# B141X.net
KiCad netlist of a schematic drawn in EAGLE
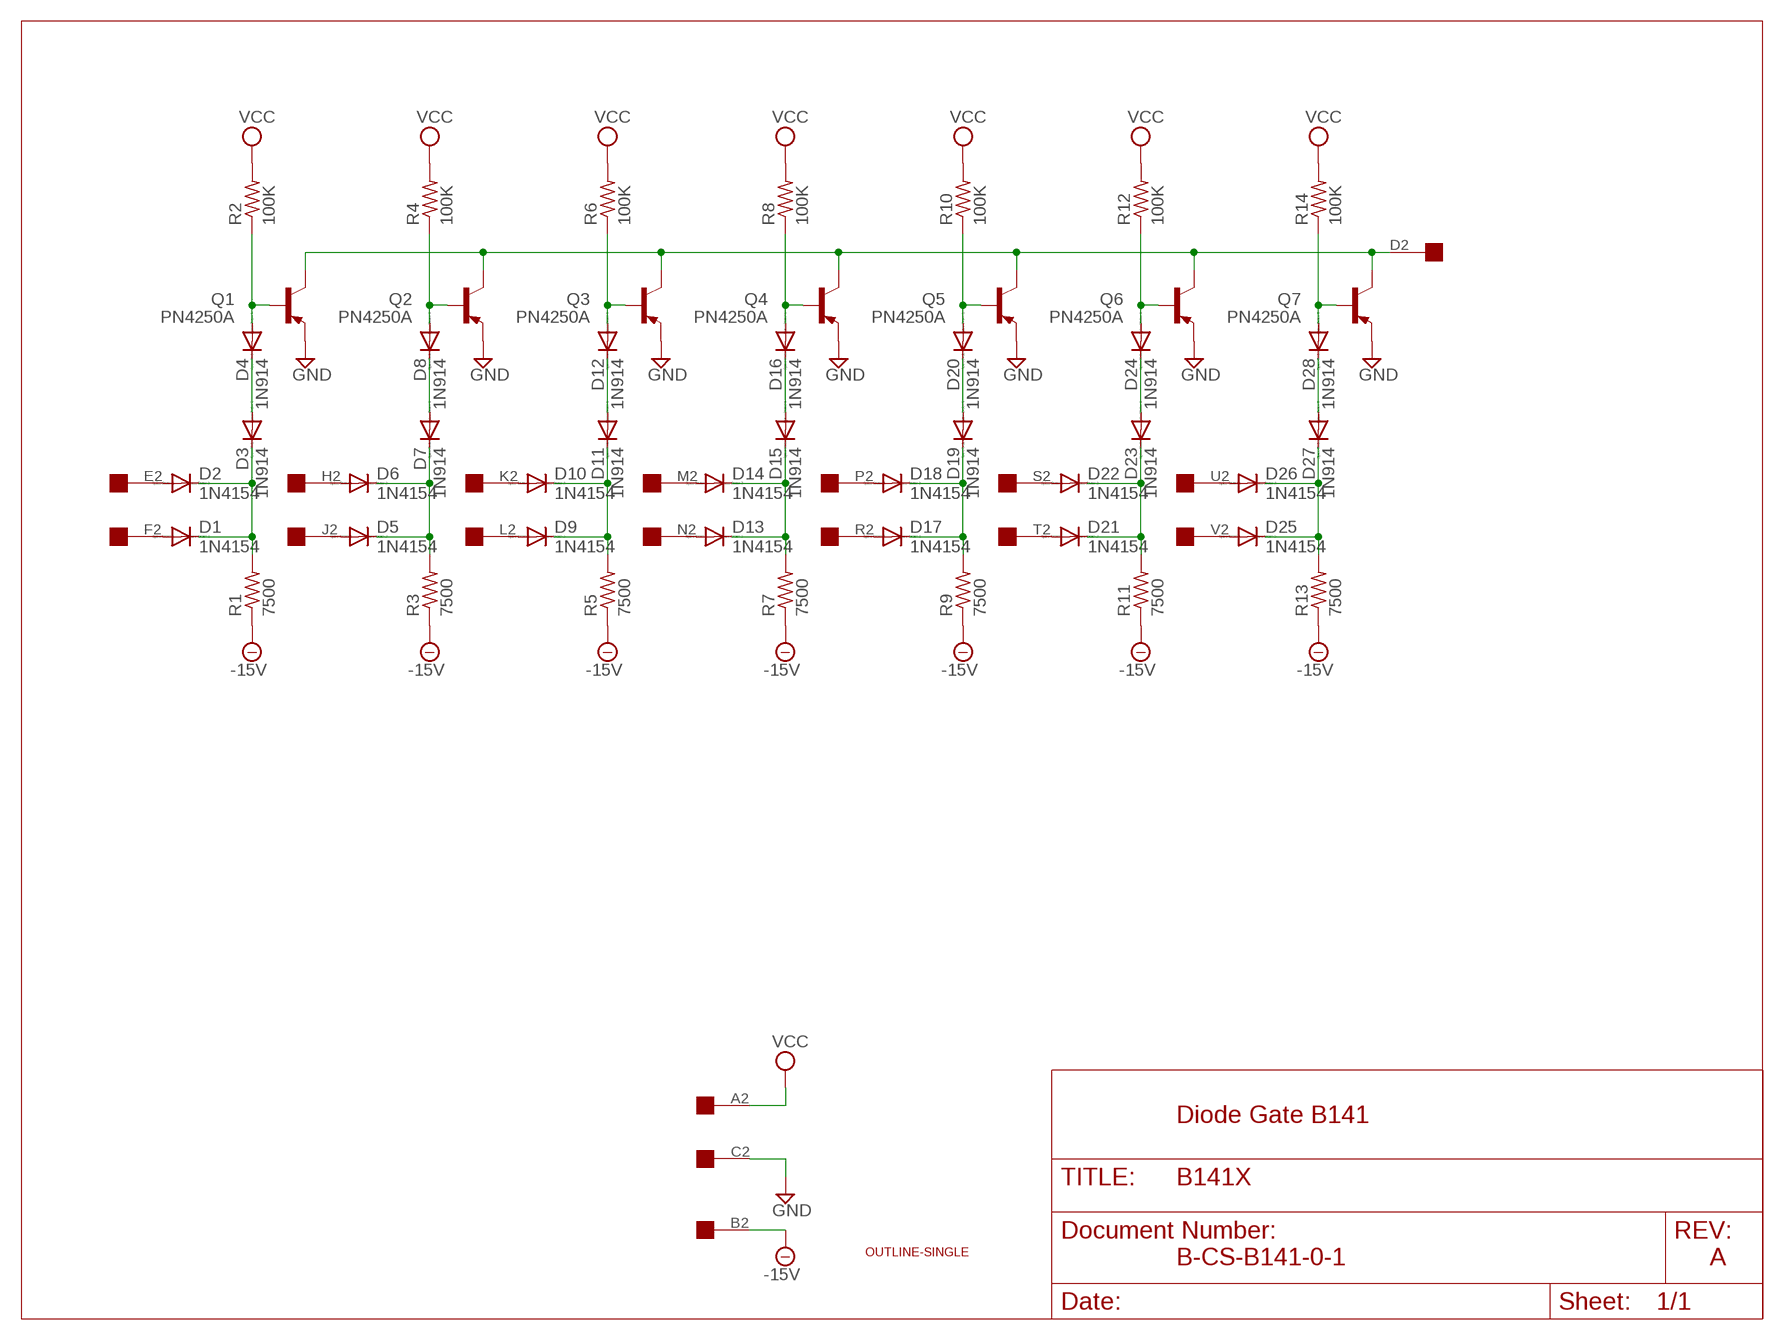
[diagram p0: schematic, sheet 1]

(export (version "E")
  (design (tool "Eeschema 10.0.6"))
  (components
    (comp (ref "D1")
      (value "1N4154")
      (footprint "eagle-import:DO35-10")
      (libsource (lib "eagle-import") (part "DIODE-DO35-10"))
    )
    (comp (ref "D2")
      (value "1N4154")
      (footprint "eagle-import:DO35-10")
      (libsource (lib "eagle-import") (part "DIODE-DO35-10"))
    )
    (comp (ref "D3")
      (value "1N914")
      (footprint "eagle-import:DO35-10")
      (libsource (lib "eagle-import") (part "DIODE-DO35-10"))
    )
    (comp (ref "D4")
      (value "1N914")
      (footprint "eagle-import:DO35-10")
      (libsource (lib "eagle-import") (part "DIODE-DO35-10"))
    )
    (comp (ref "D5")
      (value "1N4154")
      (footprint "eagle-import:DO35-10")
      (libsource (lib "eagle-import") (part "DIODE-DO35-10"))
    )
    (comp (ref "D6")
      (value "1N4154")
      (footprint "eagle-import:DO35-10")
      (libsource (lib "eagle-import") (part "DIODE-DO35-10"))
    )
    (comp (ref "D7")
      (value "1N914")
      (footprint "eagle-import:DO35-10")
      (libsource (lib "eagle-import") (part "DIODE-DO35-10"))
    )
    (comp (ref "D8")
      (value "1N914")
      (footprint "eagle-import:DO35-10")
      (libsource (lib "eagle-import") (part "DIODE-DO35-10"))
    )
    (comp (ref "D9")
      (value "1N4154")
      (footprint "eagle-import:DO35-10")
      (libsource (lib "eagle-import") (part "DIODE-DO35-10"))
    )
    (comp (ref "D10")
      (value "1N4154")
      (footprint "eagle-import:DO35-10")
      (libsource (lib "eagle-import") (part "DIODE-DO35-10"))
    )
    (comp (ref "D11")
      (value "1N914")
      (footprint "eagle-import:DO35-10")
      (libsource (lib "eagle-import") (part "DIODE-DO35-10"))
    )
    (comp (ref "D12")
      (value "1N914")
      (footprint "eagle-import:DO35-10")
      (libsource (lib "eagle-import") (part "DIODE-DO35-10"))
    )
    (comp (ref "D13")
      (value "1N4154")
      (footprint "eagle-import:DO35-10")
      (libsource (lib "eagle-import") (part "DIODE-DO35-10"))
    )
    (comp (ref "D14")
      (value "1N4154")
      (footprint "eagle-import:DO35-10")
      (libsource (lib "eagle-import") (part "DIODE-DO35-10"))
    )
    (comp (ref "D15")
      (value "1N914")
      (footprint "eagle-import:DO35-10")
      (libsource (lib "eagle-import") (part "DIODE-DO35-10"))
    )
    (comp (ref "D16")
      (value "1N914")
      (footprint "eagle-import:DO35-10")
      (libsource (lib "eagle-import") (part "DIODE-DO35-10"))
    )
    (comp (ref "D17")
      (value "1N4154")
      (footprint "eagle-import:DO35-10")
      (libsource (lib "eagle-import") (part "DIODE-DO35-10"))
    )
    (comp (ref "D18")
      (value "1N4154")
      (footprint "eagle-import:DO35-10")
      (libsource (lib "eagle-import") (part "DIODE-DO35-10"))
    )
    (comp (ref "D19")
      (value "1N914")
      (footprint "eagle-import:DO35-10")
      (libsource (lib "eagle-import") (part "DIODE-DO35-10"))
    )
    (comp (ref "D20")
      (value "1N914")
      (footprint "eagle-import:DO35-10")
      (libsource (lib "eagle-import") (part "DIODE-DO35-10"))
    )
    (comp (ref "D21")
      (value "1N4154")
      (footprint "eagle-import:DO35-10")
      (libsource (lib "eagle-import") (part "DIODE-DO35-10"))
    )
    (comp (ref "D22")
      (value "1N4154")
      (footprint "eagle-import:DO35-10")
      (libsource (lib "eagle-import") (part "DIODE-DO35-10"))
    )
    (comp (ref "D23")
      (value "1N914")
      (footprint "eagle-import:DO35-10")
      (libsource (lib "eagle-import") (part "DIODE-DO35-10"))
    )
    (comp (ref "D24")
      (value "1N914")
      (footprint "eagle-import:DO35-10")
      (libsource (lib "eagle-import") (part "DIODE-DO35-10"))
    )
    (comp (ref "D25")
      (value "1N4154")
      (footprint "eagle-import:DO35-10")
      (libsource (lib "eagle-import") (part "DIODE-DO35-10"))
    )
    (comp (ref "D26")
      (value "1N4154")
      (footprint "eagle-import:DO35-10")
      (libsource (lib "eagle-import") (part "DIODE-DO35-10"))
    )
    (comp (ref "D27")
      (value "1N914")
      (footprint "eagle-import:DO35-10")
      (libsource (lib "eagle-import") (part "DIODE-DO35-10"))
    )
    (comp (ref "D28")
      (value "1N914")
      (footprint "eagle-import:DO35-10")
      (libsource (lib "eagle-import") (part "DIODE-DO35-10"))
    )
    (comp (ref "Q1")
      (value "PN4250A")
      (footprint "eagle-import:TO5")
      (libsource (lib "eagle-import") (part "-PNP-TO5"))
    )
    (comp (ref "Q2")
      (value "PN4250A")
      (footprint "eagle-import:TO5")
      (libsource (lib "eagle-import") (part "-PNP-TO5"))
    )
    (comp (ref "Q3")
      (value "PN4250A")
      (footprint "eagle-import:TO5")
      (libsource (lib "eagle-import") (part "-PNP-TO5"))
    )
    (comp (ref "Q4")
      (value "PN4250A")
      (footprint "eagle-import:TO5")
      (libsource (lib "eagle-import") (part "-PNP-TO5"))
    )
    (comp (ref "Q5")
      (value "PN4250A")
      (footprint "eagle-import:TO5")
      (libsource (lib "eagle-import") (part "-PNP-TO5"))
    )
    (comp (ref "Q6")
      (value "PN4250A")
      (footprint "eagle-import:TO5")
      (libsource (lib "eagle-import") (part "-PNP-TO5"))
    )
    (comp (ref "Q7")
      (value "PN4250A")
      (footprint "eagle-import:TO5")
      (libsource (lib "eagle-import") (part "-PNP-TO5"))
    )
    (comp (ref "R1")
      (value "7500")
      (footprint "eagle-import:0207_10")
      (libsource (lib "eagle-import") (part "R-US_0207/10"))
    )
    (comp (ref "R2")
      (value "100K")
      (footprint "eagle-import:0207_10")
      (libsource (lib "eagle-import") (part "R-US_0207/10"))
    )
    (comp (ref "R3")
      (value "7500")
      (footprint "eagle-import:0207_10")
      (libsource (lib "eagle-import") (part "R-US_0207/10"))
    )
    (comp (ref "R4")
      (value "100K")
      (footprint "eagle-import:0207_10")
      (libsource (lib "eagle-import") (part "R-US_0207/10"))
    )
    (comp (ref "R5")
      (value "7500")
      (footprint "eagle-import:0207_10")
      (libsource (lib "eagle-import") (part "R-US_0207/10"))
    )
    (comp (ref "R6")
      (value "100K")
      (footprint "eagle-import:0207_10")
      (libsource (lib "eagle-import") (part "R-US_0207/10"))
    )
    (comp (ref "R7")
      (value "7500")
      (footprint "eagle-import:0207_10")
      (libsource (lib "eagle-import") (part "R-US_0207/10"))
    )
    (comp (ref "R8")
      (value "100K")
      (footprint "eagle-import:0207_10")
      (libsource (lib "eagle-import") (part "R-US_0207/10"))
    )
    (comp (ref "R9")
      (value "7500")
      (footprint "eagle-import:0207_10")
      (libsource (lib "eagle-import") (part "R-US_0207/10"))
    )
    (comp (ref "R10")
      (value "100K")
      (footprint "eagle-import:0207_10")
      (libsource (lib "eagle-import") (part "R-US_0207/10"))
    )
    (comp (ref "R11")
      (value "7500")
      (footprint "eagle-import:0207_10")
      (libsource (lib "eagle-import") (part "R-US_0207/10"))
    )
    (comp (ref "R12")
      (value "100K")
      (footprint "eagle-import:0207_10")
      (libsource (lib "eagle-import") (part "R-US_0207/10"))
    )
    (comp (ref "R13")
      (value "7500")
      (footprint "eagle-import:0207_10")
      (libsource (lib "eagle-import") (part "R-US_0207/10"))
    )
    (comp (ref "R14")
      (value "100K")
      (footprint "eagle-import:0207_10")
      (libsource (lib "eagle-import") (part "R-US_0207/10"))
    )
    (comp (ref "U$1")
      (value "OUTLINE-SINGLE")
      (footprint "eagle-import:SINGLE")
      (libsource (lib "eagle-import") (part "OUTLINE-SINGLE"))
    )
    (comp (ref "U$2")
      (value "EDGE-1")
      (footprint "eagle-import:EDGE-CON1")
      (libsource (lib "eagle-import") (part "EDGE-1"))
    )
  )
  (nets
    (net (code "1") (name "-15V") (class "Default")
      (node (ref "R1") (pin "1") (pinfunction "1_1") (pintype "passive"))
      (node (ref "R11") (pin "1") (pinfunction "1_1") (pintype "passive"))
      (node (ref "R13") (pin "1") (pinfunction "1_1") (pintype "passive"))
      (node (ref "R3") (pin "1") (pinfunction "1_1") (pintype "passive"))
      (node (ref "R5") (pin "1") (pinfunction "1_1") (pintype "passive"))
      (node (ref "R7") (pin "1") (pinfunction "1_1") (pintype "passive"))
      (node (ref "R9") (pin "1") (pinfunction "1_1") (pintype "passive"))
      (node (ref "U$2") (pin "B2") (pinfunction "1_B2") (pintype "bidirectional"))
    )
    (net (code "2") (name "GND") (class "Default")
      (node (ref "Q1") (pin "1") (pinfunction "E_1") (pintype "passive"))
      (node (ref "Q2") (pin "1") (pinfunction "E_1") (pintype "passive"))
      (node (ref "Q3") (pin "1") (pinfunction "E_1") (pintype "passive"))
      (node (ref "Q4") (pin "1") (pinfunction "E_1") (pintype "passive"))
      (node (ref "Q5") (pin "1") (pinfunction "E_1") (pintype "passive"))
      (node (ref "Q6") (pin "1") (pinfunction "E_1") (pintype "passive"))
      (node (ref "Q7") (pin "1") (pinfunction "E_1") (pintype "passive"))
      (node (ref "U$2") (pin "C2") (pinfunction "1_C2") (pintype "bidirectional"))
    )
    (net (code "3") (name "Net-(D1-PadC)") (class "Default")
      (node (ref "D1") (pin "C") (pinfunction "C_C") (pintype "passive"))
      (node (ref "D2") (pin "C") (pinfunction "C_C") (pintype "passive"))
      (node (ref "D3") (pin "C") (pinfunction "C_C") (pintype "passive"))
      (node (ref "R1") (pin "2") (pinfunction "2_2") (pintype "passive"))
    )
    (net (code "4") (name "Net-(D3-PadA)") (class "Default")
      (node (ref "D3") (pin "A") (pinfunction "A_A") (pintype "passive"))
      (node (ref "D4") (pin "C") (pinfunction "C_C") (pintype "passive"))
    )
    (net (code "5") (name "Net-(D5-PadC)") (class "Default")
      (node (ref "D5") (pin "C") (pinfunction "C_C") (pintype "passive"))
      (node (ref "D6") (pin "C") (pinfunction "C_C") (pintype "passive"))
      (node (ref "D7") (pin "C") (pinfunction "C_C") (pintype "passive"))
      (node (ref "R3") (pin "2") (pinfunction "2_2") (pintype "passive"))
    )
    (net (code "6") (name "Net-(D7-PadA)") (class "Default")
      (node (ref "D7") (pin "A") (pinfunction "A_A") (pintype "passive"))
      (node (ref "D8") (pin "C") (pinfunction "C_C") (pintype "passive"))
    )
    (net (code "7") (name "Net-(D10-PadC)") (class "Default")
      (node (ref "D10") (pin "C") (pinfunction "C_C") (pintype "passive"))
      (node (ref "D11") (pin "C") (pinfunction "C_C") (pintype "passive"))
      (node (ref "D9") (pin "C") (pinfunction "C_C") (pintype "passive"))
      (node (ref "R5") (pin "2") (pinfunction "2_2") (pintype "passive"))
    )
    (net (code "8") (name "Net-(D11-PadA)") (class "Default")
      (node (ref "D11") (pin "A") (pinfunction "A_A") (pintype "passive"))
      (node (ref "D12") (pin "C") (pinfunction "C_C") (pintype "passive"))
    )
    (net (code "9") (name "Net-(D13-PadC)") (class "Default")
      (node (ref "D13") (pin "C") (pinfunction "C_C") (pintype "passive"))
      (node (ref "D14") (pin "C") (pinfunction "C_C") (pintype "passive"))
      (node (ref "D15") (pin "C") (pinfunction "C_C") (pintype "passive"))
      (node (ref "R7") (pin "2") (pinfunction "2_2") (pintype "passive"))
    )
    (net (code "10") (name "Net-(D15-PadA)") (class "Default")
      (node (ref "D15") (pin "A") (pinfunction "A_A") (pintype "passive"))
      (node (ref "D16") (pin "C") (pinfunction "C_C") (pintype "passive"))
    )
    (net (code "11") (name "Net-(D17-PadC)") (class "Default")
      (node (ref "D17") (pin "C") (pinfunction "C_C") (pintype "passive"))
      (node (ref "D18") (pin "C") (pinfunction "C_C") (pintype "passive"))
      (node (ref "D19") (pin "C") (pinfunction "C_C") (pintype "passive"))
      (node (ref "R9") (pin "2") (pinfunction "2_2") (pintype "passive"))
    )
    (net (code "12") (name "Net-(D19-PadA)") (class "Default")
      (node (ref "D19") (pin "A") (pinfunction "A_A") (pintype "passive"))
      (node (ref "D20") (pin "C") (pinfunction "C_C") (pintype "passive"))
    )
    (net (code "13") (name "Net-(D21-PadC)") (class "Default")
      (node (ref "D21") (pin "C") (pinfunction "C_C") (pintype "passive"))
      (node (ref "D22") (pin "C") (pinfunction "C_C") (pintype "passive"))
      (node (ref "D23") (pin "C") (pinfunction "C_C") (pintype "passive"))
      (node (ref "R11") (pin "2") (pinfunction "2_2") (pintype "passive"))
    )
    (net (code "14") (name "Net-(D23-PadA)") (class "Default")
      (node (ref "D23") (pin "A") (pinfunction "A_A") (pintype "passive"))
      (node (ref "D24") (pin "C") (pinfunction "C_C") (pintype "passive"))
    )
    (net (code "15") (name "Net-(D25-PadC)") (class "Default")
      (node (ref "D25") (pin "C") (pinfunction "C_C") (pintype "passive"))
      (node (ref "D26") (pin "C") (pinfunction "C_C") (pintype "passive"))
      (node (ref "D27") (pin "C") (pinfunction "C_C") (pintype "passive"))
      (node (ref "R13") (pin "2") (pinfunction "2_2") (pintype "passive"))
    )
    (net (code "16") (name "Net-(D27-PadA)") (class "Default")
      (node (ref "D27") (pin "A") (pinfunction "A_A") (pintype "passive"))
      (node (ref "D28") (pin "C") (pinfunction "C_C") (pintype "passive"))
    )
    (net (code "17") (name "Net-(Q1-B)") (class "Default")
      (node (ref "D4") (pin "A") (pinfunction "A_A") (pintype "passive"))
      (node (ref "Q1") (pin "2") (pinfunction "B_2") (pintype "passive"))
      (node (ref "R2") (pin "1") (pinfunction "1_1") (pintype "passive"))
    )
    (net (code "18") (name "Net-(Q1-C)") (class "Default")
      (node (ref "Q1") (pin "3") (pinfunction "C_3") (pintype "passive"))
      (node (ref "Q2") (pin "3") (pinfunction "C_3") (pintype "passive"))
      (node (ref "Q3") (pin "3") (pinfunction "C_3") (pintype "passive"))
      (node (ref "Q4") (pin "3") (pinfunction "C_3") (pintype "passive"))
      (node (ref "Q5") (pin "3") (pinfunction "C_3") (pintype "passive"))
      (node (ref "Q6") (pin "3") (pinfunction "C_3") (pintype "passive"))
      (node (ref "Q7") (pin "3") (pinfunction "C_3") (pintype "passive"))
      (node (ref "U$2") (pin "D2") (pinfunction "1_D2") (pintype "bidirectional"))
    )
    (net (code "19") (name "Net-(Q2-B)") (class "Default")
      (node (ref "D8") (pin "A") (pinfunction "A_A") (pintype "passive"))
      (node (ref "Q2") (pin "2") (pinfunction "B_2") (pintype "passive"))
      (node (ref "R4") (pin "1") (pinfunction "1_1") (pintype "passive"))
    )
    (net (code "20") (name "Net-(Q3-B)") (class "Default")
      (node (ref "D12") (pin "A") (pinfunction "A_A") (pintype "passive"))
      (node (ref "Q3") (pin "2") (pinfunction "B_2") (pintype "passive"))
      (node (ref "R6") (pin "1") (pinfunction "1_1") (pintype "passive"))
    )
    (net (code "21") (name "Net-(Q4-B)") (class "Default")
      (node (ref "D16") (pin "A") (pinfunction "A_A") (pintype "passive"))
      (node (ref "Q4") (pin "2") (pinfunction "B_2") (pintype "passive"))
      (node (ref "R8") (pin "1") (pinfunction "1_1") (pintype "passive"))
    )
    (net (code "22") (name "Net-(Q5-B)") (class "Default")
      (node (ref "D20") (pin "A") (pinfunction "A_A") (pintype "passive"))
      (node (ref "Q5") (pin "2") (pinfunction "B_2") (pintype "passive"))
      (node (ref "R10") (pin "1") (pinfunction "1_1") (pintype "passive"))
    )
    (net (code "23") (name "Net-(Q6-B)") (class "Default")
      (node (ref "D24") (pin "A") (pinfunction "A_A") (pintype "passive"))
      (node (ref "Q6") (pin "2") (pinfunction "B_2") (pintype "passive"))
      (node (ref "R12") (pin "1") (pinfunction "1_1") (pintype "passive"))
    )
    (net (code "24") (name "Net-(Q7-B)") (class "Default")
      (node (ref "D28") (pin "A") (pinfunction "A_A") (pintype "passive"))
      (node (ref "Q7") (pin "2") (pinfunction "B_2") (pintype "passive"))
      (node (ref "R14") (pin "1") (pinfunction "1_1") (pintype "passive"))
    )
    (net (code "25") (name "Net-(U$2E-1)") (class "Default")
      (node (ref "D2") (pin "A") (pinfunction "A_A") (pintype "passive"))
      (node (ref "U$2") (pin "E2") (pinfunction "1_E2") (pintype "bidirectional"))
    )
    (net (code "26") (name "Net-(U$2F-1)") (class "Default")
      (node (ref "D1") (pin "A") (pinfunction "A_A") (pintype "passive"))
      (node (ref "U$2") (pin "F2") (pinfunction "1_F2") (pintype "bidirectional"))
    )
    (net (code "27") (name "Net-(U$2G-1)") (class "Default")
      (node (ref "D6") (pin "A") (pinfunction "A_A") (pintype "passive"))
      (node (ref "U$2") (pin "H2") (pinfunction "1_H2") (pintype "bidirectional"))
    )
    (net (code "28") (name "Net-(U$2H-1)") (class "Default")
      (node (ref "D5") (pin "A") (pinfunction "A_A") (pintype "passive"))
      (node (ref "U$2") (pin "J2") (pinfunction "1_J2") (pintype "bidirectional"))
    )
    (net (code "29") (name "Net-(U$2I-1)") (class "Default")
      (node (ref "D10") (pin "A") (pinfunction "A_A") (pintype "passive"))
      (node (ref "U$2") (pin "K2") (pinfunction "1_K2") (pintype "bidirectional"))
    )
    (net (code "30") (name "Net-(U$2J-1)") (class "Default")
      (node (ref "D9") (pin "A") (pinfunction "A_A") (pintype "passive"))
      (node (ref "U$2") (pin "L2") (pinfunction "1_L2") (pintype "bidirectional"))
    )
    (net (code "31") (name "Net-(U$2K-1)") (class "Default")
      (node (ref "D14") (pin "A") (pinfunction "A_A") (pintype "passive"))
      (node (ref "U$2") (pin "M2") (pinfunction "1_M2") (pintype "bidirectional"))
    )
    (net (code "32") (name "Net-(U$2L-1)") (class "Default")
      (node (ref "D13") (pin "A") (pinfunction "A_A") (pintype "passive"))
      (node (ref "U$2") (pin "N2") (pinfunction "1_N2") (pintype "bidirectional"))
    )
    (net (code "33") (name "Net-(U$2M-1)") (class "Default")
      (node (ref "D18") (pin "A") (pinfunction "A_A") (pintype "passive"))
      (node (ref "U$2") (pin "P2") (pinfunction "1_P2") (pintype "bidirectional"))
    )
    (net (code "34") (name "Net-(U$2N-1)") (class "Default")
      (node (ref "D17") (pin "A") (pinfunction "A_A") (pintype "passive"))
      (node (ref "U$2") (pin "R2") (pinfunction "1_R2") (pintype "bidirectional"))
    )
    (net (code "35") (name "Net-(U$2O-1)") (class "Default")
      (node (ref "D22") (pin "A") (pinfunction "A_A") (pintype "passive"))
      (node (ref "U$2") (pin "S2") (pinfunction "1_S2") (pintype "bidirectional"))
    )
    (net (code "36") (name "Net-(U$2P-1)") (class "Default")
      (node (ref "D21") (pin "A") (pinfunction "A_A") (pintype "passive"))
      (node (ref "U$2") (pin "T2") (pinfunction "1_T2") (pintype "bidirectional"))
    )
    (net (code "37") (name "Net-(U$2Q-1)") (class "Default")
      (node (ref "D26") (pin "A") (pinfunction "A_A") (pintype "passive"))
      (node (ref "U$2") (pin "U2") (pinfunction "1_U2") (pintype "bidirectional"))
    )
    (net (code "38") (name "Net-(U$2R-1)") (class "Default")
      (node (ref "D25") (pin "A") (pinfunction "A_A") (pintype "passive"))
      (node (ref "U$2") (pin "V2") (pinfunction "1_V2") (pintype "bidirectional"))
    )
    (net (code "39") (name "VCC") (class "Default")
      (node (ref "R10") (pin "2") (pinfunction "2_2") (pintype "passive"))
      (node (ref "R12") (pin "2") (pinfunction "2_2") (pintype "passive"))
      (node (ref "R14") (pin "2") (pinfunction "2_2") (pintype "passive"))
      (node (ref "R2") (pin "2") (pinfunction "2_2") (pintype "passive"))
      (node (ref "R4") (pin "2") (pinfunction "2_2") (pintype "passive"))
      (node (ref "R6") (pin "2") (pinfunction "2_2") (pintype "passive"))
      (node (ref "R8") (pin "2") (pinfunction "2_2") (pintype "passive"))
      (node (ref "U$2") (pin "A2") (pinfunction "1_A2") (pintype "bidirectional"))
    )
  )
)
